# Haptic.net
KiCad netlist of a schematic drawn in Altium Designer
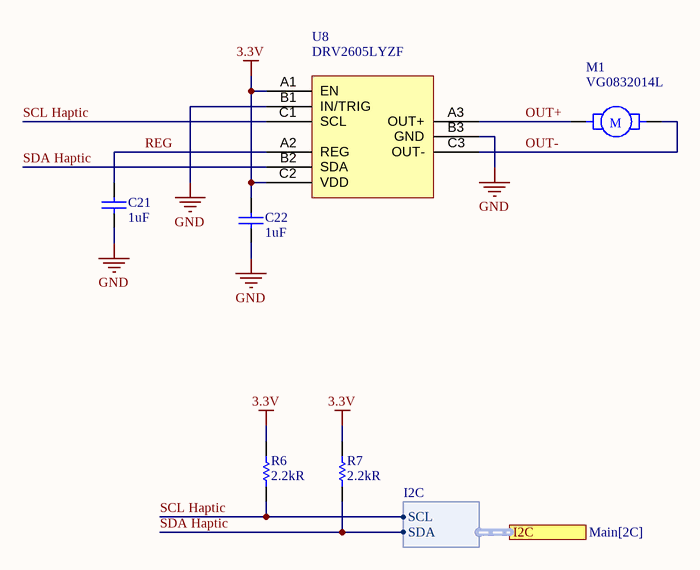
[diagram p0: Haptic.SchDoc]

(export (version "E")
  (design (tool "Eeschema 10.0.6"))
  (components
    (comp (ref "C21") (value "1uF") (footprint "Capacitor 0402") (libsource (lib "x-io") (part "Capacitor")))
    (comp (ref "C22") (value "1uF") (footprint "Capacitor 0402") (libsource (lib "x-io") (part "Capacitor")))
    (comp (ref "M1")
      (value "VG0832014L")
      (footprint "VG0832014L")
      (libsource (lib "x-io") (part "VG0832014L"))
    )
    (comp (ref "R6") (value "2.2kR") (footprint "Resistor 0402") (libsource (lib "x-io") (part "Resistor")))
    (comp (ref "R7") (value "2.2kR") (footprint "Resistor 0402") (libsource (lib "x-io") (part "Resistor")))
    (comp (ref "U8")
      (value "DRV2605LYZF")
      (footprint "DRV2605LYZF")
      (libsource (lib "x-io") (part "DRV2605LYZF"))
    )
  )
  (nets
    (net (code "2") (name "/OUT+") (class "Default")
      (node (ref "M1") (pin "1") (pinfunction "1_1") (pintype "passive"))
      (node (ref "U8") (pin "A3") (pinfunction "OUT+_A3") (pintype "passive"))
    )
    (net (code "3") (name "/OUT-") (class "Default")
      (node (ref "M1") (pin "2") (pinfunction "2_2") (pintype "passive"))
      (node (ref "U8") (pin "C3") (pinfunction "OUT-_C3") (pintype "passive"))
    )
    (net (code "4") (name "/REG") (class "Default")
      (node (ref "C21") (pin "2") (pinfunction "2_2") (pintype "passive"))
      (node (ref "U8") (pin "A2") (pinfunction "REG_A2") (pintype "passive"))
    )
    (net (code "5") (name "/SCL Haptic") (class "Default")
      (node (ref "R6") (pin "1") (pinfunction "1_1") (pintype "passive"))
      (node (ref "U8") (pin "C1") (pinfunction "SCL_C1") (pintype "passive"))
    )
    (net (code "6") (name "/SDA Haptic") (class "Default")
      (node (ref "R7") (pin "1") (pinfunction "1_1") (pintype "passive"))
      (node (ref "U8") (pin "B2") (pinfunction "SDA_B2") (pintype "passive"))
    )
    (net (code "8") (name "3.3V") (class "Default")
      (node (ref "C22") (pin "2") (pinfunction "2_2") (pintype "passive"))
      (node (ref "R6") (pin "2") (pinfunction "2_2") (pintype "passive"))
      (node (ref "R7") (pin "2") (pinfunction "2_2") (pintype "passive"))
      (node (ref "U8") (pin "A1") (pinfunction "EN_A1") (pintype "passive"))
      (node (ref "U8") (pin "C2") (pinfunction "VDD_C2") (pintype "passive"))
    )
    (net (code "9") (name "GND") (class "Default")
      (node (ref "C21") (pin "1") (pinfunction "1_1") (pintype "passive"))
      (node (ref "C22") (pin "1") (pinfunction "1_1") (pintype "passive"))
      (node (ref "U8") (pin "B1") (pinfunction "IN/TRIG_B1") (pintype "passive"))
      (node (ref "U8") (pin "B3") (pinfunction "GND_B3") (pintype "passive"))
    )
  )
)
